# SHDN-BSPD-S08-V00-Buzzer.net
KiCad netlist of a schematic drawn in Altium Designer
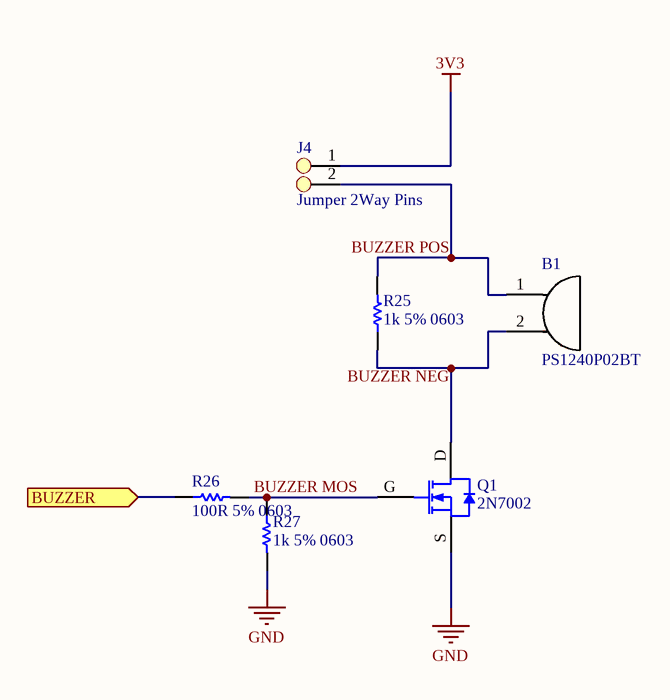
[diagram p0: SHDN-BSPD-S08-V00-Buzzer.SchDoc]

(export (version "E")
  (design (tool "Eeschema 10.0.6"))
  (components
    (comp (ref "B1")
      (value "PS1240P02BT")
      (footprint "PS1240P02BT")
      (description "Buzzers Transducer, Externally Driven Piezo 3V 4kHz 60dB @ 3V, 10cm Through Hole PC Pins")
      (libsource (lib "QUTMS_BuzzerLibrary") (part "PS1240P02BT"))
    )
    (comp (ref "J4")
      (value "Jumper 2Way Pins")
      (footprint "Jumper_2Way_Pin")
      (description "Jumper 2Way Side Pins")
      (libsource (lib "QUTMS_JumperLibrary") (part "Jumper 2Way Side Pins"))
    )
    (comp (ref "Q1")
      (value "2N7002")
      (footprint "SOT23-3")
      (libsource (lib "QUTMS_MOSFETLibrary") (part "2N7002"))
    )
    (comp (ref "R25")
      (value "1k 5% 0603")
      (footprint "Res_ThinFilm_0603")
      (description "Resistor, SMD, 1k, 0.1W, 5%, 0603")
      (libsource (lib "StandardResistors") (part "1k 5% 0603"))
    )
    (comp (ref "R26")
      (value "100R 5% 0603")
      (footprint "Res_ThinFilm_0603")
      (description "Resistor, SMD, 100R, 0.1W, 5%, 0603")
      (libsource (lib "StandardResistors") (part "100R 5%, 0603"))
    )
    (comp (ref "R27")
      (value "1k 5% 0603")
      (footprint "Res_ThinFilm_0603")
      (description "Resistor, SMD, 1k, 0.1W, 5%, 0603")
      (libsource (lib "StandardResistors") (part "1k 5% 0603"))
    )
  )
  (nets
    (net (code "1") (name "/BUZZER") (class "Default")
      (node (ref "R26") (pin "1") (pinfunction "1_1") (pintype "passive"))
    )
    (net (code "2") (name "/BUZZER MOS") (class "Default")
      (node (ref "Q1") (pin "G") (pinfunction "G_G") (pintype "passive"))
      (node (ref "R26") (pin "2") (pinfunction "2_2") (pintype "passive"))
      (node (ref "R27") (pin "1") (pinfunction "1_1") (pintype "passive"))
    )
    (net (code "3") (name "/BUZZER NEG") (class "Default")
      (node (ref "B1") (pin "2") (pinfunction "2_2") (pintype "passive"))
      (node (ref "Q1") (pin "D") (pinfunction "D_D") (pintype "passive"))
      (node (ref "R25") (pin "1") (pinfunction "1_1") (pintype "passive"))
    )
    (net (code "4") (name "/BUZZER POS") (class "Default")
      (node (ref "B1") (pin "1") (pinfunction "1_1") (pintype "passive"))
      (node (ref "J4") (pin "2") (pinfunction "2_2") (pintype "passive"))
      (node (ref "R25") (pin "2") (pinfunction "2_2") (pintype "passive"))
    )
    (net (code "5") (name "3V3") (class "Default")
      (node (ref "J4") (pin "1") (pinfunction "1_1") (pintype "passive"))
    )
    (net (code "6") (name "GND") (class "Default")
      (node (ref "Q1") (pin "S") (pinfunction "S_S") (pintype "passive"))
      (node (ref "R27") (pin "2") (pinfunction "2_2") (pintype "passive"))
    )
  )
)
